# MillingLight.net
KiCad netlist of a schematic drawn in Altium Designer
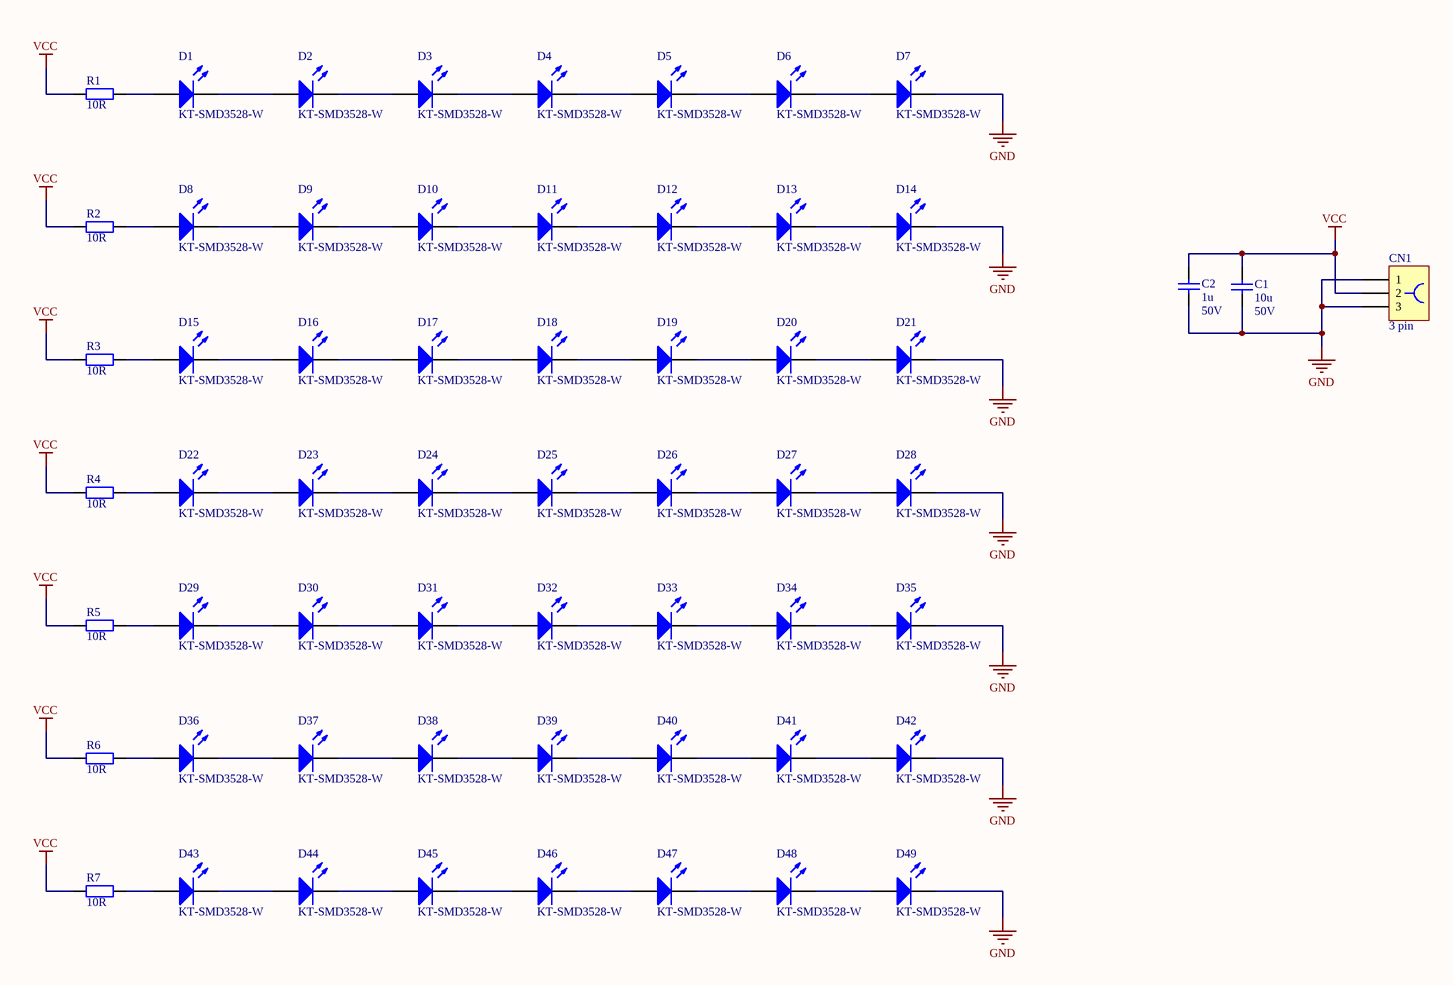
[diagram p0: MillingLight.SchDoc]

(export (version "E")
  (design (tool "Eeschema 10.0.6"))
  (components
    (comp (ref "C1")
      (value "CAP")
      (footprint "CAPC3216X18N")
      (description "CAP, MLCC, X5R, 10UF, 50V, 1206")
      (fields
        (field (name "VALUE1") "10u")
        (field (name "VALUE2") "50V")
        (field (name "MANUFACTURER") "Murata")
      )
      (libsource (lib "DSW_Lib") (part "CAP"))
    )
    (comp (ref "C2")
      (value "CAP")
      (footprint "CAPC2012X125N")
      (description "X7R 10% 0805")
      (fields
        (field (name "VALUE1") "1u")
        (field (name "VALUE2") "50V")
        (field (name "MANUFACTURER") "KEMET")
      )
      (libsource (lib "DSW_Lib") (part "CAP"))
    )
    (comp (ref "CN1")
      (value "CN_1X3F")
      (footprint "CN_WURTH_691216510003")
      (description "WURTH ELEKTRONIK 691216510003 - T/BLOCK, 5,08mm 3W")
      (fields (field (name "VALUE1") "3 pin") (field (name "MANUFACTURER") "Wurth"))
      (libsource (lib "DSW_Lib") (part "CN_1X3F"))
    )
    (comp (ref "D1")
      (value "DIO_LED")
      (footprint "DIO_Kento_KT-SMD3528-W")
      (description "High Luminous PLCC2 Power Top SMD LED")
      (fields (field (name "VALUE1") "KT-SMD3528-W") (field (name "MANUFACTURER") "Kento"))
      (libsource (lib "DSW_Lib") (part "DIO_LED"))
    )
    (comp (ref "D2")
      (value "DIO_LED")
      (footprint "DIO_Kento_KT-SMD3528-W")
      (description "High Luminous PLCC2 Power Top SMD LED")
      (fields (field (name "VALUE1") "KT-SMD3528-W") (field (name "MANUFACTURER") "Kento"))
      (libsource (lib "DSW_Lib") (part "DIO_LED"))
    )
    (comp (ref "D3")
      (value "DIO_LED")
      (footprint "DIO_Kento_KT-SMD3528-W")
      (description "High Luminous PLCC2 Power Top SMD LED")
      (fields (field (name "VALUE1") "KT-SMD3528-W") (field (name "MANUFACTURER") "Kento"))
      (libsource (lib "DSW_Lib") (part "DIO_LED"))
    )
    (comp (ref "D4")
      (value "DIO_LED")
      (footprint "DIO_Kento_KT-SMD3528-W")
      (description "High Luminous PLCC2 Power Top SMD LED")
      (fields (field (name "VALUE1") "KT-SMD3528-W") (field (name "MANUFACTURER") "Kento"))
      (libsource (lib "DSW_Lib") (part "DIO_LED"))
    )
    (comp (ref "D5")
      (value "DIO_LED")
      (footprint "DIO_Kento_KT-SMD3528-W")
      (description "High Luminous PLCC2 Power Top SMD LED")
      (fields (field (name "VALUE1") "KT-SMD3528-W") (field (name "MANUFACTURER") "Kento"))
      (libsource (lib "DSW_Lib") (part "DIO_LED"))
    )
    (comp (ref "D6")
      (value "DIO_LED")
      (footprint "DIO_Kento_KT-SMD3528-W")
      (description "High Luminous PLCC2 Power Top SMD LED")
      (fields (field (name "VALUE1") "KT-SMD3528-W") (field (name "MANUFACTURER") "Kento"))
      (libsource (lib "DSW_Lib") (part "DIO_LED"))
    )
    (comp (ref "D7")
      (value "DIO_LED")
      (footprint "DIO_Kento_KT-SMD3528-W")
      (description "High Luminous PLCC2 Power Top SMD LED")
      (fields (field (name "VALUE1") "KT-SMD3528-W") (field (name "MANUFACTURER") "Kento"))
      (libsource (lib "DSW_Lib") (part "DIO_LED"))
    )
    (comp (ref "D8")
      (value "DIO_LED")
      (footprint "DIO_Kento_KT-SMD3528-W")
      (description "High Luminous PLCC2 Power Top SMD LED")
      (fields (field (name "VALUE1") "KT-SMD3528-W") (field (name "MANUFACTURER") "Kento"))
      (libsource (lib "DSW_Lib") (part "DIO_LED"))
    )
    (comp (ref "D9")
      (value "DIO_LED")
      (footprint "DIO_Kento_KT-SMD3528-W")
      (description "High Luminous PLCC2 Power Top SMD LED")
      (fields (field (name "VALUE1") "KT-SMD3528-W") (field (name "MANUFACTURER") "Kento"))
      (libsource (lib "DSW_Lib") (part "DIO_LED"))
    )
    (comp (ref "D10")
      (value "DIO_LED")
      (footprint "DIO_Kento_KT-SMD3528-W")
      (description "High Luminous PLCC2 Power Top SMD LED")
      (fields (field (name "VALUE1") "KT-SMD3528-W") (field (name "MANUFACTURER") "Kento"))
      (libsource (lib "DSW_Lib") (part "DIO_LED"))
    )
    (comp (ref "D11")
      (value "DIO_LED")
      (footprint "DIO_Kento_KT-SMD3528-W")
      (description "High Luminous PLCC2 Power Top SMD LED")
      (fields (field (name "VALUE1") "KT-SMD3528-W") (field (name "MANUFACTURER") "Kento"))
      (libsource (lib "DSW_Lib") (part "DIO_LED"))
    )
    (comp (ref "D12")
      (value "DIO_LED")
      (footprint "DIO_Kento_KT-SMD3528-W")
      (description "High Luminous PLCC2 Power Top SMD LED")
      (fields (field (name "VALUE1") "KT-SMD3528-W") (field (name "MANUFACTURER") "Kento"))
      (libsource (lib "DSW_Lib") (part "DIO_LED"))
    )
    (comp (ref "D13")
      (value "DIO_LED")
      (footprint "DIO_Kento_KT-SMD3528-W")
      (description "High Luminous PLCC2 Power Top SMD LED")
      (fields (field (name "VALUE1") "KT-SMD3528-W") (field (name "MANUFACTURER") "Kento"))
      (libsource (lib "DSW_Lib") (part "DIO_LED"))
    )
    (comp (ref "D14")
      (value "DIO_LED")
      (footprint "DIO_Kento_KT-SMD3528-W")
      (description "High Luminous PLCC2 Power Top SMD LED")
      (fields (field (name "VALUE1") "KT-SMD3528-W") (field (name "MANUFACTURER") "Kento"))
      (libsource (lib "DSW_Lib") (part "DIO_LED"))
    )
    (comp (ref "D15")
      (value "DIO_LED")
      (footprint "DIO_Kento_KT-SMD3528-W")
      (description "High Luminous PLCC2 Power Top SMD LED")
      (fields (field (name "VALUE1") "KT-SMD3528-W") (field (name "MANUFACTURER") "Kento"))
      (libsource (lib "DSW_Lib") (part "DIO_LED"))
    )
    (comp (ref "D16")
      (value "DIO_LED")
      (footprint "DIO_Kento_KT-SMD3528-W")
      (description "High Luminous PLCC2 Power Top SMD LED")
      (fields (field (name "VALUE1") "KT-SMD3528-W") (field (name "MANUFACTURER") "Kento"))
      (libsource (lib "DSW_Lib") (part "DIO_LED"))
    )
    (comp (ref "D17")
      (value "DIO_LED")
      (footprint "DIO_Kento_KT-SMD3528-W")
      (description "High Luminous PLCC2 Power Top SMD LED")
      (fields (field (name "VALUE1") "KT-SMD3528-W") (field (name "MANUFACTURER") "Kento"))
      (libsource (lib "DSW_Lib") (part "DIO_LED"))
    )
    (comp (ref "D18")
      (value "DIO_LED")
      (footprint "DIO_Kento_KT-SMD3528-W")
      (description "High Luminous PLCC2 Power Top SMD LED")
      (fields (field (name "VALUE1") "KT-SMD3528-W") (field (name "MANUFACTURER") "Kento"))
      (libsource (lib "DSW_Lib") (part "DIO_LED"))
    )
    (comp (ref "D19")
      (value "DIO_LED")
      (footprint "DIO_Kento_KT-SMD3528-W")
      (description "High Luminous PLCC2 Power Top SMD LED")
      (fields (field (name "VALUE1") "KT-SMD3528-W") (field (name "MANUFACTURER") "Kento"))
      (libsource (lib "DSW_Lib") (part "DIO_LED"))
    )
    (comp (ref "D20")
      (value "DIO_LED")
      (footprint "DIO_Kento_KT-SMD3528-W")
      (description "High Luminous PLCC2 Power Top SMD LED")
      (fields (field (name "VALUE1") "KT-SMD3528-W") (field (name "MANUFACTURER") "Kento"))
      (libsource (lib "DSW_Lib") (part "DIO_LED"))
    )
    (comp (ref "D21")
      (value "DIO_LED")
      (footprint "DIO_Kento_KT-SMD3528-W")
      (description "High Luminous PLCC2 Power Top SMD LED")
      (fields (field (name "VALUE1") "KT-SMD3528-W") (field (name "MANUFACTURER") "Kento"))
      (libsource (lib "DSW_Lib") (part "DIO_LED"))
    )
    (comp (ref "D22")
      (value "DIO_LED")
      (footprint "DIO_Kento_KT-SMD3528-W")
      (description "High Luminous PLCC2 Power Top SMD LED")
      (fields (field (name "VALUE1") "KT-SMD3528-W") (field (name "MANUFACTURER") "Kento"))
      (libsource (lib "DSW_Lib") (part "DIO_LED"))
    )
    (comp (ref "D23")
      (value "DIO_LED")
      (footprint "DIO_Kento_KT-SMD3528-W")
      (description "High Luminous PLCC2 Power Top SMD LED")
      (fields (field (name "VALUE1") "KT-SMD3528-W") (field (name "MANUFACTURER") "Kento"))
      (libsource (lib "DSW_Lib") (part "DIO_LED"))
    )
    (comp (ref "D24")
      (value "DIO_LED")
      (footprint "DIO_Kento_KT-SMD3528-W")
      (description "High Luminous PLCC2 Power Top SMD LED")
      (fields (field (name "VALUE1") "KT-SMD3528-W") (field (name "MANUFACTURER") "Kento"))
      (libsource (lib "DSW_Lib") (part "DIO_LED"))
    )
    (comp (ref "D25")
      (value "DIO_LED")
      (footprint "DIO_Kento_KT-SMD3528-W")
      (description "High Luminous PLCC2 Power Top SMD LED")
      (fields (field (name "VALUE1") "KT-SMD3528-W") (field (name "MANUFACTURER") "Kento"))
      (libsource (lib "DSW_Lib") (part "DIO_LED"))
    )
    (comp (ref "D26")
      (value "DIO_LED")
      (footprint "DIO_Kento_KT-SMD3528-W")
      (description "High Luminous PLCC2 Power Top SMD LED")
      (fields (field (name "VALUE1") "KT-SMD3528-W") (field (name "MANUFACTURER") "Kento"))
      (libsource (lib "DSW_Lib") (part "DIO_LED"))
    )
    (comp (ref "D27")
      (value "DIO_LED")
      (footprint "DIO_Kento_KT-SMD3528-W")
      (description "High Luminous PLCC2 Power Top SMD LED")
      (fields (field (name "VALUE1") "KT-SMD3528-W") (field (name "MANUFACTURER") "Kento"))
      (libsource (lib "DSW_Lib") (part "DIO_LED"))
    )
    (comp (ref "D28")
      (value "DIO_LED")
      (footprint "DIO_Kento_KT-SMD3528-W")
      (description "High Luminous PLCC2 Power Top SMD LED")
      (fields (field (name "VALUE1") "KT-SMD3528-W") (field (name "MANUFACTURER") "Kento"))
      (libsource (lib "DSW_Lib") (part "DIO_LED"))
    )
    (comp (ref "D29")
      (value "DIO_LED")
      (footprint "DIO_Kento_KT-SMD3528-W")
      (description "High Luminous PLCC2 Power Top SMD LED")
      (fields (field (name "VALUE1") "KT-SMD3528-W") (field (name "MANUFACTURER") "Kento"))
      (libsource (lib "DSW_Lib") (part "DIO_LED"))
    )
    (comp (ref "D30")
      (value "DIO_LED")
      (footprint "DIO_Kento_KT-SMD3528-W")
      (description "High Luminous PLCC2 Power Top SMD LED")
      (fields (field (name "VALUE1") "KT-SMD3528-W") (field (name "MANUFACTURER") "Kento"))
      (libsource (lib "DSW_Lib") (part "DIO_LED"))
    )
    (comp (ref "D31")
      (value "DIO_LED")
      (footprint "DIO_Kento_KT-SMD3528-W")
      (description "High Luminous PLCC2 Power Top SMD LED")
      (fields (field (name "VALUE1") "KT-SMD3528-W") (field (name "MANUFACTURER") "Kento"))
      (libsource (lib "DSW_Lib") (part "DIO_LED"))
    )
    (comp (ref "D32")
      (value "DIO_LED")
      (footprint "DIO_Kento_KT-SMD3528-W")
      (description "High Luminous PLCC2 Power Top SMD LED")
      (fields (field (name "VALUE1") "KT-SMD3528-W") (field (name "MANUFACTURER") "Kento"))
      (libsource (lib "DSW_Lib") (part "DIO_LED"))
    )
    (comp (ref "D33")
      (value "DIO_LED")
      (footprint "DIO_Kento_KT-SMD3528-W")
      (description "High Luminous PLCC2 Power Top SMD LED")
      (fields (field (name "VALUE1") "KT-SMD3528-W") (field (name "MANUFACTURER") "Kento"))
      (libsource (lib "DSW_Lib") (part "DIO_LED"))
    )
    (comp (ref "D34")
      (value "DIO_LED")
      (footprint "DIO_Kento_KT-SMD3528-W")
      (description "High Luminous PLCC2 Power Top SMD LED")
      (fields (field (name "VALUE1") "KT-SMD3528-W") (field (name "MANUFACTURER") "Kento"))
      (libsource (lib "DSW_Lib") (part "DIO_LED"))
    )
    (comp (ref "D35")
      (value "DIO_LED")
      (footprint "DIO_Kento_KT-SMD3528-W")
      (description "High Luminous PLCC2 Power Top SMD LED")
      (fields (field (name "VALUE1") "KT-SMD3528-W") (field (name "MANUFACTURER") "Kento"))
      (libsource (lib "DSW_Lib") (part "DIO_LED"))
    )
    (comp (ref "D36")
      (value "DIO_LED")
      (footprint "DIO_Kento_KT-SMD3528-W")
      (description "High Luminous PLCC2 Power Top SMD LED")
      (fields (field (name "VALUE1") "KT-SMD3528-W") (field (name "MANUFACTURER") "Kento"))
      (libsource (lib "DSW_Lib") (part "DIO_LED"))
    )
    (comp (ref "D37")
      (value "DIO_LED")
      (footprint "DIO_Kento_KT-SMD3528-W")
      (description "High Luminous PLCC2 Power Top SMD LED")
      (fields (field (name "VALUE1") "KT-SMD3528-W") (field (name "MANUFACTURER") "Kento"))
      (libsource (lib "DSW_Lib") (part "DIO_LED"))
    )
    (comp (ref "D38")
      (value "DIO_LED")
      (footprint "DIO_Kento_KT-SMD3528-W")
      (description "High Luminous PLCC2 Power Top SMD LED")
      (fields (field (name "VALUE1") "KT-SMD3528-W") (field (name "MANUFACTURER") "Kento"))
      (libsource (lib "DSW_Lib") (part "DIO_LED"))
    )
    (comp (ref "D39")
      (value "DIO_LED")
      (footprint "DIO_Kento_KT-SMD3528-W")
      (description "High Luminous PLCC2 Power Top SMD LED")
      (fields (field (name "VALUE1") "KT-SMD3528-W") (field (name "MANUFACTURER") "Kento"))
      (libsource (lib "DSW_Lib") (part "DIO_LED"))
    )
    (comp (ref "D40")
      (value "DIO_LED")
      (footprint "DIO_Kento_KT-SMD3528-W")
      (description "High Luminous PLCC2 Power Top SMD LED")
      (fields (field (name "VALUE1") "KT-SMD3528-W") (field (name "MANUFACTURER") "Kento"))
      (libsource (lib "DSW_Lib") (part "DIO_LED"))
    )
    (comp (ref "D41")
      (value "DIO_LED")
      (footprint "DIO_Kento_KT-SMD3528-W")
      (description "High Luminous PLCC2 Power Top SMD LED")
      (fields (field (name "VALUE1") "KT-SMD3528-W") (field (name "MANUFACTURER") "Kento"))
      (libsource (lib "DSW_Lib") (part "DIO_LED"))
    )
    (comp (ref "D42")
      (value "DIO_LED")
      (footprint "DIO_Kento_KT-SMD3528-W")
      (description "High Luminous PLCC2 Power Top SMD LED")
      (fields (field (name "VALUE1") "KT-SMD3528-W") (field (name "MANUFACTURER") "Kento"))
      (libsource (lib "DSW_Lib") (part "DIO_LED"))
    )
    (comp (ref "D43")
      (value "DIO_LED")
      (footprint "DIO_Kento_KT-SMD3528-W")
      (description "High Luminous PLCC2 Power Top SMD LED")
      (fields (field (name "VALUE1") "KT-SMD3528-W") (field (name "MANUFACTURER") "Kento"))
      (libsource (lib "DSW_Lib") (part "DIO_LED"))
    )
    (comp (ref "D44")
      (value "DIO_LED")
      (footprint "DIO_Kento_KT-SMD3528-W")
      (description "High Luminous PLCC2 Power Top SMD LED")
      (fields (field (name "VALUE1") "KT-SMD3528-W") (field (name "MANUFACTURER") "Kento"))
      (libsource (lib "DSW_Lib") (part "DIO_LED"))
    )
    (comp (ref "D45")
      (value "DIO_LED")
      (footprint "DIO_Kento_KT-SMD3528-W")
      (description "High Luminous PLCC2 Power Top SMD LED")
      (fields (field (name "VALUE1") "KT-SMD3528-W") (field (name "MANUFACTURER") "Kento"))
      (libsource (lib "DSW_Lib") (part "DIO_LED"))
    )
    (comp (ref "D46")
      (value "DIO_LED")
      (footprint "DIO_Kento_KT-SMD3528-W")
      (description "High Luminous PLCC2 Power Top SMD LED")
      (fields (field (name "VALUE1") "KT-SMD3528-W") (field (name "MANUFACTURER") "Kento"))
      (libsource (lib "DSW_Lib") (part "DIO_LED"))
    )
    (comp (ref "D47")
      (value "DIO_LED")
      (footprint "DIO_Kento_KT-SMD3528-W")
      (description "High Luminous PLCC2 Power Top SMD LED")
      (fields (field (name "VALUE1") "KT-SMD3528-W") (field (name "MANUFACTURER") "Kento"))
      (libsource (lib "DSW_Lib") (part "DIO_LED"))
    )
    (comp (ref "D48")
      (value "DIO_LED")
      (footprint "DIO_Kento_KT-SMD3528-W")
      (description "High Luminous PLCC2 Power Top SMD LED")
      (fields (field (name "VALUE1") "KT-SMD3528-W") (field (name "MANUFACTURER") "Kento"))
      (libsource (lib "DSW_Lib") (part "DIO_LED"))
    )
    (comp (ref "D49")
      (value "DIO_LED")
      (footprint "DIO_Kento_KT-SMD3528-W")
      (description "High Luminous PLCC2 Power Top SMD LED")
      (fields (field (name "VALUE1") "KT-SMD3528-W") (field (name "MANUFACTURER") "Kento"))
      (libsource (lib "DSW_Lib") (part "DIO_LED"))
    )
    (comp (ref "R1")
      (value "RES")
      (footprint "RESC2012X60N")
      (description "RESISTOR, 0805, 10R, 1%, SMD")
      (fields (field (name "VALUE1") "10R") (field (name "MANUFACTURER") "Yageo"))
      (libsource (lib "DSW_Lib") (part "RES"))
    )
    (comp (ref "R2")
      (value "RES")
      (footprint "RESC2012X60N")
      (description "RESISTOR, 0805, 10R, 1%, SMD")
      (fields (field (name "VALUE1") "10R") (field (name "MANUFACTURER") "Yageo"))
      (libsource (lib "DSW_Lib") (part "RES"))
    )
    (comp (ref "R3")
      (value "RES")
      (footprint "RESC2012X60N")
      (description "RESISTOR, 0805, 10R, 1%, SMD")
      (fields (field (name "VALUE1") "10R") (field (name "MANUFACTURER") "Yageo"))
      (libsource (lib "DSW_Lib") (part "RES"))
    )
    (comp (ref "R4")
      (value "RES")
      (footprint "RESC2012X60N")
      (description "RESISTOR, 0805, 10R, 1%, SMD")
      (fields (field (name "VALUE1") "10R") (field (name "MANUFACTURER") "Yageo"))
      (libsource (lib "DSW_Lib") (part "RES"))
    )
    (comp (ref "R5")
      (value "RES")
      (footprint "RESC2012X60N")
      (description "RESISTOR, 0805, 10R, 1%, SMD")
      (fields (field (name "VALUE1") "10R") (field (name "MANUFACTURER") "Yageo"))
      (libsource (lib "DSW_Lib") (part "RES"))
    )
    (comp (ref "R6")
      (value "RES")
      (footprint "RESC2012X60N")
      (description "RESISTOR, 0805, 10R, 1%, SMD")
      (fields (field (name "VALUE1") "10R") (field (name "MANUFACTURER") "Yageo"))
      (libsource (lib "DSW_Lib") (part "RES"))
    )
    (comp (ref "R7")
      (value "RES")
      (footprint "RESC2012X60N")
      (description "RESISTOR, 0805, 10R, 1%, SMD")
      (fields (field (name "VALUE1") "10R") (field (name "MANUFACTURER") "Yageo"))
      (libsource (lib "DSW_Lib") (part "RES"))
    )
  )
  (nets
    (net (code "1") (name "GND") (class "Default")
      (node (ref "C1") (pin "1") (pinfunction "1_1") (pintype "passive"))
      (node (ref "C2") (pin "1") (pinfunction "1_1") (pintype "passive"))
      (node (ref "CN1") (pin "1") (pinfunction "1_1") (pintype "passive"))
      (node (ref "CN1") (pin "3") (pinfunction "3_3") (pintype "passive"))
      (node (ref "D14") (pin "1") (pinfunction "K_1") (pintype "passive"))
      (node (ref "D21") (pin "1") (pinfunction "K_1") (pintype "passive"))
      (node (ref "D28") (pin "1") (pinfunction "K_1") (pintype "passive"))
      (node (ref "D35") (pin "1") (pinfunction "K_1") (pintype "passive"))
      (node (ref "D42") (pin "1") (pinfunction "K_1") (pintype "passive"))
      (node (ref "D49") (pin "1") (pinfunction "K_1") (pintype "passive"))
      (node (ref "D7") (pin "1") (pinfunction "K_1") (pintype "passive"))
    )
    (net (code "2") (name "Net-(D1-A)") (class "Default")
      (node (ref "D1") (pin "2") (pinfunction "A_2") (pintype "passive"))
      (node (ref "R1") (pin "2") (pinfunction "2_2") (pintype "passive"))
    )
    (net (code "3") (name "Net-(D1-K)") (class "Default")
      (node (ref "D1") (pin "1") (pinfunction "K_1") (pintype "passive"))
      (node (ref "D2") (pin "2") (pinfunction "A_2") (pintype "passive"))
    )
    (net (code "4") (name "Net-(D2-K)") (class "Default")
      (node (ref "D2") (pin "1") (pinfunction "K_1") (pintype "passive"))
      (node (ref "D3") (pin "2") (pinfunction "A_2") (pintype "passive"))
    )
    (net (code "5") (name "Net-(D3-K)") (class "Default")
      (node (ref "D3") (pin "1") (pinfunction "K_1") (pintype "passive"))
      (node (ref "D4") (pin "2") (pinfunction "A_2") (pintype "passive"))
    )
    (net (code "6") (name "Net-(D4-K)") (class "Default")
      (node (ref "D4") (pin "1") (pinfunction "K_1") (pintype "passive"))
      (node (ref "D5") (pin "2") (pinfunction "A_2") (pintype "passive"))
    )
    (net (code "7") (name "Net-(D5-K)") (class "Default")
      (node (ref "D5") (pin "1") (pinfunction "K_1") (pintype "passive"))
      (node (ref "D6") (pin "2") (pinfunction "A_2") (pintype "passive"))
    )
    (net (code "8") (name "Net-(D6-K)") (class "Default")
      (node (ref "D6") (pin "1") (pinfunction "K_1") (pintype "passive"))
      (node (ref "D7") (pin "2") (pinfunction "A_2") (pintype "passive"))
    )
    (net (code "9") (name "Net-(D8-A)") (class "Default")
      (node (ref "D8") (pin "2") (pinfunction "A_2") (pintype "passive"))
      (node (ref "R2") (pin "2") (pinfunction "2_2") (pintype "passive"))
    )
    (net (code "10") (name "Net-(D8-K)") (class "Default")
      (node (ref "D8") (pin "1") (pinfunction "K_1") (pintype "passive"))
      (node (ref "D9") (pin "2") (pinfunction "A_2") (pintype "passive"))
    )
    (net (code "11") (name "Net-(D10-A)") (class "Default")
      (node (ref "D10") (pin "2") (pinfunction "A_2") (pintype "passive"))
      (node (ref "D9") (pin "1") (pinfunction "K_1") (pintype "passive"))
    )
    (net (code "12") (name "Net-(D10-K)") (class "Default")
      (node (ref "D10") (pin "1") (pinfunction "K_1") (pintype "passive"))
      (node (ref "D11") (pin "2") (pinfunction "A_2") (pintype "passive"))
    )
    (net (code "13") (name "Net-(D11-K)") (class "Default")
      (node (ref "D11") (pin "1") (pinfunction "K_1") (pintype "passive"))
      (node (ref "D12") (pin "2") (pinfunction "A_2") (pintype "passive"))
    )
    (net (code "14") (name "Net-(D12-K)") (class "Default")
      (node (ref "D12") (pin "1") (pinfunction "K_1") (pintype "passive"))
      (node (ref "D13") (pin "2") (pinfunction "A_2") (pintype "passive"))
    )
    (net (code "15") (name "Net-(D13-K)") (class "Default")
      (node (ref "D13") (pin "1") (pinfunction "K_1") (pintype "passive"))
      (node (ref "D14") (pin "2") (pinfunction "A_2") (pintype "passive"))
    )
    (net (code "16") (name "Net-(D15-A)") (class "Default")
      (node (ref "D15") (pin "2") (pinfunction "A_2") (pintype "passive"))
      (node (ref "R3") (pin "2") (pinfunction "2_2") (pintype "passive"))
    )
    (net (code "17") (name "Net-(D15-K)") (class "Default")
      (node (ref "D15") (pin "1") (pinfunction "K_1") (pintype "passive"))
      (node (ref "D16") (pin "2") (pinfunction "A_2") (pintype "passive"))
    )
    (net (code "18") (name "Net-(D16-K)") (class "Default")
      (node (ref "D16") (pin "1") (pinfunction "K_1") (pintype "passive"))
      (node (ref "D17") (pin "2") (pinfunction "A_2") (pintype "passive"))
    )
    (net (code "19") (name "Net-(D17-K)") (class "Default")
      (node (ref "D17") (pin "1") (pinfunction "K_1") (pintype "passive"))
      (node (ref "D18") (pin "2") (pinfunction "A_2") (pintype "passive"))
    )
    (net (code "20") (name "Net-(D18-K)") (class "Default")
      (node (ref "D18") (pin "1") (pinfunction "K_1") (pintype "passive"))
      (node (ref "D19") (pin "2") (pinfunction "A_2") (pintype "passive"))
    )
    (net (code "21") (name "Net-(D19-K)") (class "Default")
      (node (ref "D19") (pin "1") (pinfunction "K_1") (pintype "passive"))
      (node (ref "D20") (pin "2") (pinfunction "A_2") (pintype "passive"))
    )
    (net (code "22") (name "Net-(D20-K)") (class "Default")
      (node (ref "D20") (pin "1") (pinfunction "K_1") (pintype "passive"))
      (node (ref "D21") (pin "2") (pinfunction "A_2") (pintype "passive"))
    )
    (net (code "23") (name "Net-(D22-A)") (class "Default")
      (node (ref "D22") (pin "2") (pinfunction "A_2") (pintype "passive"))
      (node (ref "R4") (pin "2") (pinfunction "2_2") (pintype "passive"))
    )
    (net (code "24") (name "Net-(D22-K)") (class "Default")
      (node (ref "D22") (pin "1") (pinfunction "K_1") (pintype "passive"))
      (node (ref "D23") (pin "2") (pinfunction "A_2") (pintype "passive"))
    )
    (net (code "25") (name "Net-(D23-K)") (class "Default")
      (node (ref "D23") (pin "1") (pinfunction "K_1") (pintype "passive"))
      (node (ref "D24") (pin "2") (pinfunction "A_2") (pintype "passive"))
    )
    (net (code "26") (name "Net-(D24-K)") (class "Default")
      (node (ref "D24") (pin "1") (pinfunction "K_1") (pintype "passive"))
      (node (ref "D25") (pin "2") (pinfunction "A_2") (pintype "passive"))
    )
    (net (code "27") (name "Net-(D25-K)") (class "Default")
      (node (ref "D25") (pin "1") (pinfunction "K_1") (pintype "passive"))
      (node (ref "D26") (pin "2") (pinfunction "A_2") (pintype "passive"))
    )
    (net (code "28") (name "Net-(D26-K)") (class "Default")
      (node (ref "D26") (pin "1") (pinfunction "K_1") (pintype "passive"))
      (node (ref "D27") (pin "2") (pinfunction "A_2") (pintype "passive"))
    )
    (net (code "29") (name "Net-(D27-K)") (class "Default")
      (node (ref "D27") (pin "1") (pinfunction "K_1") (pintype "passive"))
      (node (ref "D28") (pin "2") (pinfunction "A_2") (pintype "passive"))
    )
    (net (code "30") (name "Net-(D29-A)") (class "Default")
      (node (ref "D29") (pin "2") (pinfunction "A_2") (pintype "passive"))
      (node (ref "R5") (pin "2") (pinfunction "2_2") (pintype "passive"))
    )
    (net (code "31") (name "Net-(D29-K)") (class "Default")
      (node (ref "D29") (pin "1") (pinfunction "K_1") (pintype "passive"))
      (node (ref "D30") (pin "2") (pinfunction "A_2") (pintype "passive"))
    )
    (net (code "32") (name "Net-(D30-K)") (class "Default")
      (node (ref "D30") (pin "1") (pinfunction "K_1") (pintype "passive"))
      (node (ref "D31") (pin "2") (pinfunction "A_2") (pintype "passive"))
    )
    (net (code "33") (name "Net-(D31-K)") (class "Default")
      (node (ref "D31") (pin "1") (pinfunction "K_1") (pintype "passive"))
      (node (ref "D32") (pin "2") (pinfunction "A_2") (pintype "passive"))
    )
    (net (code "34") (name "Net-(D32-K)") (class "Default")
      (node (ref "D32") (pin "1") (pinfunction "K_1") (pintype "passive"))
      (node (ref "D33") (pin "2") (pinfunction "A_2") (pintype "passive"))
    )
    (net (code "35") (name "Net-(D33-K)") (class "Default")
      (node (ref "D33") (pin "1") (pinfunction "K_1") (pintype "passive"))
      (node (ref "D34") (pin "2") (pinfunction "A_2") (pintype "passive"))
    )
    (net (code "36") (name "Net-(D34-K)") (class "Default")
      (node (ref "D34") (pin "1") (pinfunction "K_1") (pintype "passive"))
      (node (ref "D35") (pin "2") (pinfunction "A_2") (pintype "passive"))
    )
    (net (code "37") (name "Net-(D36-A)") (class "Default")
      (node (ref "D36") (pin "2") (pinfunction "A_2") (pintype "passive"))
      (node (ref "R6") (pin "2") (pinfunction "2_2") (pintype "passive"))
    )
    (net (code "38") (name "Net-(D36-K)") (class "Default")
      (node (ref "D36") (pin "1") (pinfunction "K_1") (pintype "passive"))
      (node (ref "D37") (pin "2") (pinfunction "A_2") (pintype "passive"))
    )
    (net (code "39") (name "Net-(D37-K)") (class "Default")
      (node (ref "D37") (pin "1") (pinfunction "K_1") (pintype "passive"))
      (node (ref "D38") (pin "2") (pinfunction "A_2") (pintype "passive"))
    )
    (net (code "40") (name "Net-(D38-K)") (class "Default")
      (node (ref "D38") (pin "1") (pinfunction "K_1") (pintype "passive"))
      (node (ref "D39") (pin "2") (pinfunction "A_2") (pintype "passive"))
    )
    (net (code "41") (name "Net-(D39-K)") (class "Default")
      (node (ref "D39") (pin "1") (pinfunction "K_1") (pintype "passive"))
      (node (ref "D40") (pin "2") (pinfunction "A_2") (pintype "passive"))
    )
    (net (code "42") (name "Net-(D40-K)") (class "Default")
      (node (ref "D40") (pin "1") (pinfunction "K_1") (pintype "passive"))
      (node (ref "D41") (pin "2") (pinfunction "A_2") (pintype "passive"))
    )
    (net (code "43") (name "Net-(D41-K)") (class "Default")
      (node (ref "D41") (pin "1") (pinfunction "K_1") (pintype "passive"))
      (node (ref "D42") (pin "2") (pinfunction "A_2") (pintype "passive"))
    )
    (net (code "44") (name "Net-(D43-A)") (class "Default")
      (node (ref "D43") (pin "2") (pinfunction "A_2") (pintype "passive"))
      (node (ref "R7") (pin "2") (pinfunction "2_2") (pintype "passive"))
    )
    (net (code "45") (name "Net-(D43-K)") (class "Default")
      (node (ref "D43") (pin "1") (pinfunction "K_1") (pintype "passive"))
      (node (ref "D44") (pin "2") (pinfunction "A_2") (pintype "passive"))
    )
    (net (code "46") (name "Net-(D44-K)") (class "Default")
      (node (ref "D44") (pin "1") (pinfunction "K_1") (pintype "passive"))
      (node (ref "D45") (pin "2") (pinfunction "A_2") (pintype "passive"))
    )
    (net (code "47") (name "Net-(D45-K)") (class "Default")
      (node (ref "D45") (pin "1") (pinfunction "K_1") (pintype "passive"))
      (node (ref "D46") (pin "2") (pinfunction "A_2") (pintype "passive"))
    )
    (net (code "48") (name "Net-(D46-K)") (class "Default")
      (node (ref "D46") (pin "1") (pinfunction "K_1") (pintype "passive"))
      (node (ref "D47") (pin "2") (pinfunction "A_2") (pintype "passive"))
    )
    (net (code "49") (name "Net-(D47-K)") (class "Default")
      (node (ref "D47") (pin "1") (pinfunction "K_1") (pintype "passive"))
      (node (ref "D48") (pin "2") (pinfunction "A_2") (pintype "passive"))
    )
    (net (code "50") (name "Net-(D48-K)") (class "Default")
      (node (ref "D48") (pin "1") (pinfunction "K_1") (pintype "passive"))
      (node (ref "D49") (pin "2") (pinfunction "A_2") (pintype "passive"))
    )
    (net (code "51") (name "VCC") (class "Default")
      (node (ref "C1") (pin "2") (pinfunction "2_2") (pintype "passive"))
      (node (ref "C2") (pin "2") (pinfunction "2_2") (pintype "passive"))
      (node (ref "CN1") (pin "2") (pinfunction "2_2") (pintype "passive"))
      (node (ref "R1") (pin "1") (pinfunction "1_1") (pintype "passive"))
      (node (ref "R2") (pin "1") (pinfunction "1_1") (pintype "passive"))
      (node (ref "R3") (pin "1") (pinfunction "1_1") (pintype "passive"))
      (node (ref "R4") (pin "1") (pinfunction "1_1") (pintype "passive"))
      (node (ref "R5") (pin "1") (pinfunction "1_1") (pintype "passive"))
      (node (ref "R6") (pin "1") (pinfunction "1_1") (pintype "passive"))
      (node (ref "R7") (pin "1") (pinfunction "1_1") (pintype "passive"))
    )
  )
)
